# untitled.net
KiCad netlist of a schematic drawn in EAGLE
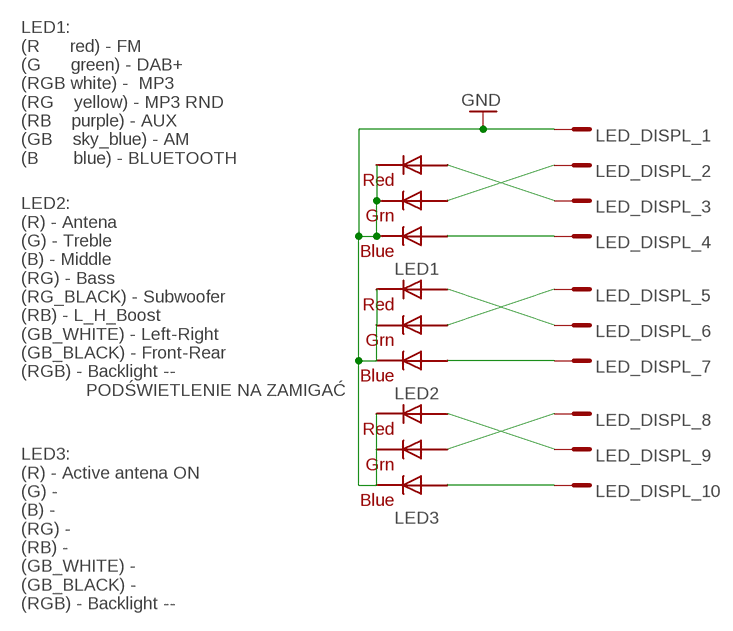
[diagram p0: schematic, sheet 1]

(export (version "E")
  (design (tool "Eeschema 10.0.6"))
  (components
    (comp (ref "LED1")
      (value "RGBLED5050")
      (footprint "eagle-import:RGBLED5050")
      (libsource (lib "eagle-import") (part "RGBLED5050"))
    )
    (comp (ref "LED2")
      (value "RGBLED5050")
      (footprint "eagle-import:RGBLED5050")
      (libsource (lib "eagle-import") (part "RGBLED5050"))
    )
    (comp (ref "LED3")
      (value "RGBLED5050")
      (footprint "eagle-import:RGBLED5050")
      (libsource (lib "eagle-import") (part "RGBLED5050"))
    )
    (comp (ref "LED_DISPL")
      (value "JST_10_PIN_B10B-PH-SM4-TB")
      (footprint "eagle-import:S10B-PH-SM4-TB")
      (libsource (lib "eagle-import") (part "JST_10_PIN_B10B-PH-SM4-TB"))
    )
  )
  (nets
    (net (code "1") (name "GND") (class "Default")
      (node (ref "LED1") (pin "4") (pinfunction "BLUE_C_4") (pintype "bidirectional"))
      (node (ref "LED1") (pin "5") (pinfunction "RED_C_5") (pintype "bidirectional"))
      (node (ref "LED1") (pin "6") (pinfunction "GREEN_C_6") (pintype "bidirectional"))
      (node (ref "LED2") (pin "4") (pinfunction "BLUE_C_4") (pintype "bidirectional"))
      (node (ref "LED2") (pin "5") (pinfunction "RED_C_5") (pintype "bidirectional"))
      (node (ref "LED2") (pin "6") (pinfunction "GREEN_C_6") (pintype "bidirectional"))
      (node (ref "LED3") (pin "4") (pinfunction "BLUE_C_4") (pintype "bidirectional"))
      (node (ref "LED3") (pin "5") (pinfunction "RED_C_5") (pintype "bidirectional"))
      (node (ref "LED3") (pin "6") (pinfunction "GREEN_C_6") (pintype "bidirectional"))
      (node (ref "LED_DISPL") (pin "P$1") (pinfunction "P$1_P$1") (pintype "bidirectional"))
    )
    (net (code "2") (name "Net-(LED1-BLUE_A)") (class "Default")
      (node (ref "LED1") (pin "3") (pinfunction "BLUE_A_3") (pintype "bidirectional"))
      (node (ref "LED_DISPL") (pin "P$4") (pinfunction "P$1_P$4") (pintype "bidirectional"))
    )
    (net (code "3") (name "Net-(LED1-GREEN_A)") (class "Default")
      (node (ref "LED1") (pin "1") (pinfunction "GREEN_A_1") (pintype "bidirectional"))
      (node (ref "LED_DISPL") (pin "P$2") (pinfunction "P$1_P$2") (pintype "bidirectional"))
    )
    (net (code "4") (name "Net-(LED1-RED_A)") (class "Default")
      (node (ref "LED1") (pin "2") (pinfunction "RED_A_2") (pintype "bidirectional"))
      (node (ref "LED_DISPL") (pin "P$3") (pinfunction "P$1_P$3") (pintype "bidirectional"))
    )
    (net (code "5") (name "Net-(LED2-BLUE_A)") (class "Default")
      (node (ref "LED2") (pin "3") (pinfunction "BLUE_A_3") (pintype "bidirectional"))
      (node (ref "LED_DISPL") (pin "P$7") (pinfunction "P$1_P$7") (pintype "bidirectional"))
    )
    (net (code "6") (name "Net-(LED2-GREEN_A)") (class "Default")
      (node (ref "LED2") (pin "1") (pinfunction "GREEN_A_1") (pintype "bidirectional"))
      (node (ref "LED_DISPL") (pin "P$5") (pinfunction "P$1_P$5") (pintype "bidirectional"))
    )
    (net (code "7") (name "Net-(LED2-RED_A)") (class "Default")
      (node (ref "LED2") (pin "2") (pinfunction "RED_A_2") (pintype "bidirectional"))
      (node (ref "LED_DISPL") (pin "P$6") (pinfunction "P$1_P$6") (pintype "bidirectional"))
    )
    (net (code "8") (name "Net-(LED3-BLUE_A)") (class "Default")
      (node (ref "LED3") (pin "3") (pinfunction "BLUE_A_3") (pintype "bidirectional"))
      (node (ref "LED_DISPL") (pin "P$10") (pinfunction "P$1_P$10") (pintype "bidirectional"))
    )
    (net (code "9") (name "Net-(LED3-GREEN_A)") (class "Default")
      (node (ref "LED3") (pin "1") (pinfunction "GREEN_A_1") (pintype "bidirectional"))
      (node (ref "LED_DISPL") (pin "P$8") (pinfunction "P$1_P$8") (pintype "bidirectional"))
    )
    (net (code "10") (name "Net-(LED3-RED_A)") (class "Default")
      (node (ref "LED3") (pin "2") (pinfunction "RED_A_2") (pintype "bidirectional"))
      (node (ref "LED_DISPL") (pin "P$9") (pinfunction "P$1_P$9") (pintype "bidirectional"))
    )
  )
)
